# ColdBlock_PID_Main01.net
KiCad netlist of a schematic drawn in Altium Designer
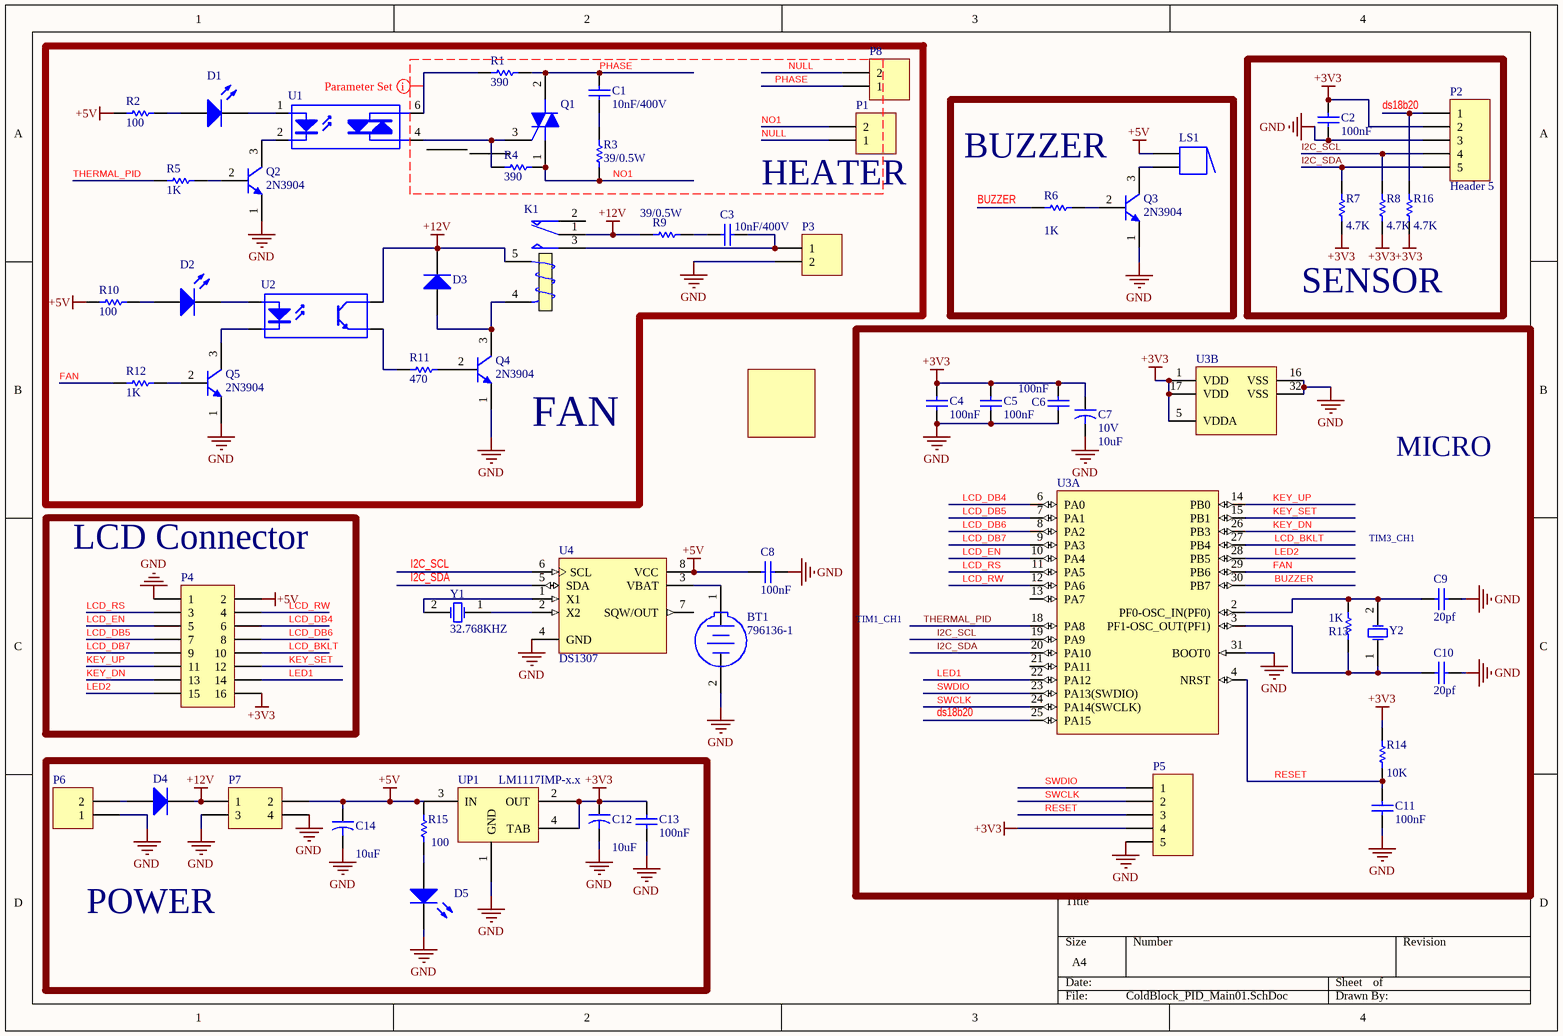
[diagram p0: ColdBlock_PID_Main01.SchDoc]

(export (version "E")
  (design (tool "Eeschema 10.0.6"))
  (components
    (comp (ref "*") (value "Logo") (footprint "LOGO_PARS_TOP") (libsource (lib "Mofidi3D") (part "Logo")))
    (comp (ref "BT1")
      (value "796136-1")
      (footprint "BTH2032_dip")
      (description "Battery Connector, 1 Cell, CR2032, 2-Pin SMD, RoHS, Tape and Reel")
      (libsource (lib "TE PCB Connectors") (part "796136-1"))
    )
    (comp (ref "C1")
      (value "10nF/400V")
      (footprint "Cap_polyester_400V")
      (description "Capacitor")
      (fields (field (name "PUBLISHER") "Altium Limited"))
      (libsource (lib "Miscellaneous Devices") (part "Cap"))
    )
    (comp (ref "C2")
      (value "100nF")
      (footprint "CAP_MLCC_RAD_0.1")
      (description "Capacitor")
      (fields (field (name "Comment") "Cap") (field (name "PUBLISHER") "Altium Limited"))
      (libsource (lib "Miscellaneous Devices") (part "Cap"))
    )
    (comp (ref "C3")
      (value "10nF/400V")
      (footprint "Cap_polyester_400V")
      (description "Capacitor")
      (fields (field (name "PUBLISHER") "Altium Limited"))
      (libsource (lib "Miscellaneous Devices") (part "Cap"))
    )
    (comp (ref "C4")
      (value "100nF")
      (footprint "CAP_MLCC_RAD_0.1")
      (description "Capacitor")
      (fields (field (name "Comment") "Cap") (field (name "PUBLISHER") "Altium Limited"))
      (libsource (lib "Miscellaneous Devices") (part "Cap"))
    )
    (comp (ref "C5")
      (value "100nF")
      (footprint "CAP_MLCC_RAD_0.1")
      (description "Capacitor")
      (fields (field (name "Comment") "Cap") (field (name "PUBLISHER") "Altium Limited"))
      (libsource (lib "Miscellaneous Devices") (part "Cap"))
    )
    (comp (ref "C6")
      (value "100nF")
      (footprint "CAP_MLCC_RAD_0.1")
      (description "Capacitor")
      (fields (field (name "Comment") "Cap") (field (name "PUBLISHER") "Altium Limited"))
      (libsource (lib "Miscellaneous Devices") (part "Cap"))
    )
    (comp (ref "C7")
      (value "10V")
      (footprint "Cap electrolitic radial 5x11-2")
      (description "Capacitor")
      (fields (field (name "ALTIUM_VALUE") "10uF") (field (name "PUBLISHER") "Altium Limited"))
      (libsource (lib "Miscellaneous Devices") (part "Cap2"))
    )
    (comp (ref "C8")
      (value "100nF")
      (footprint "CAP_MLCC_RAD_0.1")
      (description "Capacitor")
      (fields (field (name "Comment") "Cap") (field (name "PUBLISHER") "Altium Limited"))
      (libsource (lib "Miscellaneous Devices") (part "Cap"))
    )
    (comp (ref "C9")
      (value "20pf")
      (footprint "CAP_MLCC_RAD_0.1")
      (description "Capacitor")
      (fields (field (name "Comment") "Cap") (field (name "PUBLISHER") "Altium Limited"))
      (libsource (lib "Miscellaneous Devices") (part "Cap"))
    )
    (comp (ref "C10")
      (value "20pf")
      (footprint "CAP_MLCC_RAD_0.1")
      (description "Capacitor")
      (fields (field (name "Comment") "Cap") (field (name "PUBLISHER") "Altium Limited"))
      (libsource (lib "Miscellaneous Devices") (part "Cap"))
    )
    (comp (ref "C11")
      (value "100nF")
      (footprint "CAP_MLCC_RAD_0.1")
      (description "Capacitor")
      (fields (field (name "Comment") "Cap") (field (name "PUBLISHER") "Altium Limited"))
      (libsource (lib "Miscellaneous Devices") (part "Cap"))
    )
    (comp (ref "C12")
      (value "10uF")
      (footprint "Cap electrolitic radial 5x11-2")
      (description "Capacitor")
      (fields (field (name "Comment") "16V") (field (name "PUBLISHER") "Altium Limited"))
      (libsource (lib "Miscellaneous Devices") (part "Cap2"))
    )
    (comp (ref "C13")
      (value "100nF")
      (footprint "CAP_MLCC_RAD_0.1")
      (description "Capacitor")
      (fields (field (name "Comment") "Cap") (field (name "PUBLISHER") "Altium Limited"))
      (libsource (lib "Miscellaneous Devices") (part "Cap"))
    )
    (comp (ref "C14")
      (value "10uF")
      (footprint "Cap electrolitic radial 5x11-2")
      (description "Capacitor")
      (fields (field (name "Comment") "25 V") (field (name "PUBLISHER") "Altium Limited"))
      (libsource (lib "Miscellaneous Devices") (part "Cap2"))
    )
    (comp (ref "D1")
      (value "LED1")
      (footprint "LED5MM_BLUE")
      (description "Typical RED GaAs LED")
      (fields (field (name "PUBLISHER") "Altium Limited"))
      (libsource (lib "Miscellaneous Devices") (part "LED1"))
    )
    (comp (ref "D2")
      (value "LED1")
      (footprint "LED5MM_RED")
      (description "Typical RED GaAs LED")
      (fields (field (name "PUBLISHER") "Altium Limited"))
      (libsource (lib "Miscellaneous Devices") (part "LED1"))
    )
    (comp (ref "D3")
      (value "Diode 1N4007")
      (footprint "do-204al")
      (description "1 Amp General Purpose Rectifier")
      (fields (field (name "PUBLISHER") "Altium Limited"))
      (libsource (lib "Miscellaneous Devices") (part "Diode 1N4007"))
    )
    (comp (ref "D4")
      (value "1N4007")
      (footprint "DO-204AL")
      (description "Default Diode")
      (fields (field (name "PUBLISHER") "Altium Limited"))
      (libsource (lib "Miscellaneous Devices") (part "Diode"))
    )
    (comp (ref "D5")
      (value "LED0")
      (footprint "LED5MM_BLUE")
      (description "Typical INFRARED GaAs LED")
      (fields (field (name "PUBLISHER") "Altium Limited"))
      (libsource (lib "Miscellaneous Devices") (part "LED0"))
    )
    (comp (ref "K1")
      (value "Relay/12V")
      (footprint "Mofidi3D:Relay 18.85x15.35x15.70")
      (description "SPDT Relay")
      (fields (field (name "PUBLISHER") "Altium Limited"))
      (libsource (lib "Miscellaneous Devices") (part "Relay"))
    )
    (comp (ref "LS1")
      (value "Buzzer")
      (footprint "BUZZER_12A05")
      (description "Magnetic Transducer Buzzer")
      (fields (field (name "PUBLISHER") "Altium Limited"))
      (libsource (lib "Miscellaneous Devices") (part "Buzzer"))
    )
    (comp (ref "P1")
      (value "Header 2")
      (footprint "KF301 2PIN")
      (description "Header, 2-Pin")
      (fields (field (name "PUBLISHER") "Altium Limited"))
      (libsource (lib "") (part "Header 2_1"))
    )
    (comp (ref "P2")
      (value "Header 5")
      (footprint "HDR1X5")
      (description "Header, 5-Pin")
      (fields (field (name "PUBLISHER") "Altium Limited"))
      (libsource (lib "Miscellaneous Connectors") (part "Header 5"))
    )
    (comp (ref "P3")
      (value "Header 2")
      (footprint "KF301 2PIN")
      (description "Header, 2-Pin")
      (fields (field (name "PUBLISHER") "Altium Limited"))
      (libsource (lib "") (part "Header 2_2"))
    )
    (comp (ref "P4")
      (value "Header 8X2")
      (footprint "IDC2.54_16PIN")
      (description "Header, 8-Pin, Dual row")
      (fields (field (name "PUBLISHER") "Altium Limited"))
      (libsource (lib "Miscellaneous Connectors") (part "Header 8X2"))
    )
    (comp (ref "P5")
      (value "Header 5")
      (footprint "HDR_1x6")
      (description "Header, 5-Pin")
      (fields (field (name "PUBLISHER") "Altium Limited"))
      (libsource (lib "Miscellaneous Connectors") (part "Header 5"))
    )
    (comp (ref "P6")
      (value "Header 2")
      (footprint "KF301 2PIN")
      (description "Header, 2-Pin")
      (fields (field (name "PUBLISHER") "Altium Limited"))
      (libsource (lib "Miscellaneous Connectors") (part "Header 2"))
    )
    (comp (ref "P7")
      (value "MINI-360")
      (footprint "MINI360-DCDC")
      (description "Header, 2-Pin, Dual row")
      (fields (field (name "PUBLISHER") "Altium Limited"))
      (libsource (lib "Miscellaneous Connectors") (part "Header 2X2"))
    )
    (comp (ref "P8")
      (value "Header 2")
      (footprint "KF301 2PIN")
      (description "Header, 2-Pin")
      (fields (field (name "PUBLISHER") "Altium Limited"))
      (libsource (lib "") (part "Header 2_1"))
    )
    (comp (ref "Q1")
      (value "BT139")
      (footprint "TO-220 AB")
      (description "Silicon Bidirectional Triode Thyristor")
      (fields (field (name "PUBLISHER") "Altium Limited"))
      (libsource (lib "Miscellaneous Devices") (part "Triac"))
    )
    (comp (ref "Q2")
      (value "2N3904")
      (footprint "TO-92 STR")
      (description "NPN General Purpose Amplifier")
      (fields (field (name "PUBLISHER") "Altium Limited"))
      (libsource (lib "Miscellaneous Devices") (part "2N3904"))
    )
    (comp (ref "Q3")
      (value "2N3904")
      (footprint "TO-92 STR")
      (description "NPN General Purpose Amplifier")
      (fields (field (name "PUBLISHER") "Altium Limited"))
      (libsource (lib "Miscellaneous Devices") (part "2N3904"))
    )
    (comp (ref "Q4")
      (value "2N3904")
      (footprint "TO-92 STR")
      (description "NPN General Purpose Amplifier")
      (fields (field (name "PUBLISHER") "Altium Limited"))
      (libsource (lib "Miscellaneous Devices") (part "2N3904"))
    )
    (comp (ref "Q5")
      (value "2N3904")
      (footprint "TO-92 STR")
      (description "NPN General Purpose Amplifier")
      (fields (field (name "PUBLISHER") "Altium Limited"))
      (libsource (lib "Miscellaneous Devices") (part "2N3904"))
    )
    (comp (ref "R1")
      (value "390")
      (footprint "Axial 0_5W 5_0mm")
      (description "Resistor")
      (fields (field (name "Comment") "Res1") (field (name "PUBLISHER") "Altium Limited"))
      (libsource (lib "Miscellaneous Devices") (part "Res1"))
    )
    (comp (ref "R2")
      (value "100")
      (footprint "Axial 0_25 W, 0_4 IN LEAD PITCH")
      (description "Resistor")
      (fields (field (name "Comment") "Res1") (field (name "PUBLISHER") "Altium Limited"))
      (libsource (lib "Miscellaneous Devices") (part "Res1"))
    )
    (comp (ref "R3")
      (value "39/0.5W")
      (footprint "Axial 0_5W 5_0mm")
      (description "Resistor")
      (fields (field (name "Comment") "Res1") (field (name "PUBLISHER") "Altium Limited"))
      (libsource (lib "Miscellaneous Devices") (part "Res1"))
    )
    (comp (ref "R4")
      (value "390")
      (footprint "Axial 0_5W 5_0mm")
      (description "Resistor")
      (fields (field (name "Comment") "Res1") (field (name "PUBLISHER") "Altium Limited"))
      (libsource (lib "Miscellaneous Devices") (part "Res1"))
    )
    (comp (ref "R5")
      (value "1K")
      (footprint "Axial 0_25 W, 0_4 IN LEAD PITCH")
      (description "Resistor")
      (fields (field (name "Comment") "Res1") (field (name "PUBLISHER") "Altium Limited"))
      (libsource (lib "Miscellaneous Devices") (part "Res1"))
    )
    (comp (ref "R6")
      (value "1K")
      (footprint "Axial 0_25 W, 0_4 IN LEAD PITCH")
      (description "Resistor")
      (fields (field (name "Comment") "Res1") (field (name "PUBLISHER") "Altium Limited"))
      (libsource (lib "Miscellaneous Devices") (part "Res1"))
    )
    (comp (ref "R7")
      (value "4.7K")
      (footprint "Axial 0_25 W, 0_4 IN LEAD PITCH")
      (description "Resistor")
      (fields (field (name "Comment") "Res1") (field (name "PUBLISHER") "Altium Limited"))
      (libsource (lib "Miscellaneous Devices") (part "Res1"))
    )
    (comp (ref "R8")
      (value "4.7K")
      (footprint "Axial 0_25 W, 0_4 IN LEAD PITCH")
      (description "Resistor")
      (fields (field (name "Comment") "Res1") (field (name "PUBLISHER") "Altium Limited"))
      (libsource (lib "Miscellaneous Devices") (part "Res1"))
    )
    (comp (ref "R9")
      (value "39/0.5W")
      (footprint "Axial 0_5W 5_0mm")
      (description "Resistor")
      (fields (field (name "Comment") "Res1") (field (name "PUBLISHER") "Altium Limited"))
      (libsource (lib "Miscellaneous Devices") (part "Res1"))
    )
    (comp (ref "R10")
      (value "100")
      (footprint "Axial 0_25 W, 0_4 IN LEAD PITCH")
      (description "Resistor")
      (fields (field (name "Comment") "Res1") (field (name "PUBLISHER") "Altium Limited"))
      (libsource (lib "Miscellaneous Devices") (part "Res1"))
    )
    (comp (ref "R11")
      (value "470")
      (footprint "Axial 0_25 W, 0_4 IN LEAD PITCH")
      (description "Resistor")
      (fields (field (name "Comment") "Res1") (field (name "PUBLISHER") "Altium Limited"))
      (libsource (lib "Miscellaneous Devices") (part "Res1"))
    )
    (comp (ref "R12")
      (value "1K")
      (footprint "Axial 0_25 W, 0_4 IN LEAD PITCH")
      (description "Resistor")
      (fields (field (name "Comment") "Res1") (field (name "PUBLISHER") "Altium Limited"))
      (libsource (lib "Miscellaneous Devices") (part "Res1"))
    )
    (comp (ref "R13")
      (value "1K")
      (footprint "Axial 0_25 W, 0_4 IN LEAD PITCH")
      (description "Resistor")
      (fields (field (name "Comment") "Res1") (field (name "PUBLISHER") "Altium Limited"))
      (libsource (lib "Miscellaneous Devices") (part "Res1"))
    )
    (comp (ref "R14")
      (value "10K")
      (footprint "Axial 0_25 W, 0_4 IN LEAD PITCH")
      (description "Resistor")
      (fields (field (name "Comment") "Res1") (field (name "PUBLISHER") "Altium Limited"))
      (libsource (lib "Miscellaneous Devices") (part "Res1"))
    )
    (comp (ref "R15")
      (value "100")
      (footprint "Axial 0_25 W, 0_4 IN LEAD PITCH")
      (description "Resistor")
      (fields (field (name "Comment") "Res1") (field (name "PUBLISHER") "Altium Limited"))
      (libsource (lib "Miscellaneous Devices") (part "Res1"))
    )
    (comp (ref "R16")
      (value "4.7K")
      (footprint "Axial 0_25 W, 0_4 IN LEAD PITCH")
      (description "Resistor")
      (fields (field (name "Comment") "Res1") (field (name "PUBLISHER") "Altium Limited"))
      (libsource (lib "Miscellaneous Devices") (part "Res1"))
    )
    (comp (ref "U1")
      (value "MOC3063")
      (footprint "MOC3063")
      (description "Opto-Triac")
      (fields (field (name "PUBLISHER") "Altium Limited"))
      (libsource (lib "Miscellaneous Devices") (part "Opto TRIAC"))
    )
    (comp (ref "U2")
      (value "PC817")
      (footprint "DIP_4")
      (description "4-Pin Phototransistor Optocoupler")
      (fields (field (name "PUBLISHER") "Altium Limited"))
      (libsource (lib "Miscellaneous Devices") (part "Optoisolator1"))
    )
    (comp (ref "U3")
      (value "STM32F030K6T6")
      (footprint "STM-LQFP32_N")
      (libsource (lib "STMicroelectronics STM32 F0") (part "STM32F030K6T6"))
    )
    (comp (ref "U4")
      (value "DS1307")
      (footprint "DIP8")
      (description "64 X 8 Serial Real-Time Clock")
      (fields (field (name "PUBLISHER") "Altium Limited"))
      (libsource (lib "Dallas Peripheral Real Time Clock") (part "DS1307"))
    )
    (comp (ref "UP1")
      (value "LM1117IMP-x.x")
      (footprint "SOT223_4")
      (description "x.x Volt, 800mA Low-Dropout Linear Regulator, 4-pin SOT-223")
      (fields (field (name "DESIGNER") "Abbas Basereh"))
      (libsource (lib "Mofidi3D") (part "LM1117IMP-x.x"))
    )
    (comp (ref "Y1")
      (value "32.768KHZ")
      (footprint "Crystal_NC308")
      (description "Crystal Oscillator")
      (fields (field (name "PUBLISHER") "Altium Limited"))
      (libsource (lib "ECS Crystal Oscillator") (part "ECS-110-S-5P"))
    )
    (comp (ref "Y2")
      (value "8MHz")
      (footprint "CRYSTAL Small")
      (description "Crystal Oscillator")
      (fields (field (name "PUBLISHER") "Altium Limited"))
      (libsource (lib "ECS Crystal Oscillator") (part "ECS-110-S-5P"))
    )
  )
  (nets
    (net (code "1") (name "+3V3") (class "Default")
      (node (ref "C12") (pin "1") (pinfunction "1_1") (pintype "passive"))
      (node (ref "C13") (pin "2") (pinfunction "2_2") (pintype "passive"))
      (node (ref "C2") (pin "2") (pinfunction "2_2") (pintype "passive"))
      (node (ref "C4") (pin "2") (pinfunction "2_2") (pintype "passive"))
      (node (ref "C5") (pin "2") (pinfunction "2_2") (pintype "passive"))
      (node (ref "C6") (pin "2") (pinfunction "2_2") (pintype "passive"))
      (node (ref "C7") (pin "1") (pinfunction "1_1") (pintype "passive"))
      (node (ref "P2") (pin "2") (pinfunction "2_2") (pintype "passive"))
      (node (ref "P4") (pin "16") (pinfunction "16_16") (pintype "passive"))
      (node (ref "P5") (pin "4") (pinfunction "4_4") (pintype "passive"))
      (node (ref "R14") (pin "1") (pinfunction "1_1") (pintype "passive"))
      (node (ref "R16") (pin "2") (pinfunction "2_2") (pintype "passive"))
      (node (ref "R7") (pin "2") (pinfunction "2_2") (pintype "passive"))
      (node (ref "R8") (pin "2") (pinfunction "2_2") (pintype "passive"))
      (node (ref "U3") (pin "1") (pinfunction "VDD_1") (pintype "power_in"))
      (node (ref "U3") (pin "17") (pinfunction "VDD_17") (pintype "power_in"))
      (node (ref "U3") (pin "5") (pinfunction "VDDA_5") (pintype "power_in"))
      (node (ref "UP1") (pin "2") (pinfunction "OUT_2") (pintype "power_in"))
      (node (ref "UP1") (pin "4") (pinfunction "TAB_4") (pintype "power_in"))
    )
    (net (code "2") (name "+5V") (class "Default")
      (node (ref "C14") (pin "1") (pinfunction "1_1") (pintype "passive"))
      (node (ref "C8") (pin "1") (pinfunction "1_1") (pintype "passive"))
      (node (ref "LS1") (pin "1") (pinfunction "1_1") (pintype "passive"))
      (node (ref "P4") (pin "2") (pinfunction "2_2") (pintype "passive"))
      (node (ref "P7") (pin "2") (pinfunction "2_2") (pintype "passive"))
      (node (ref "R10") (pin "1") (pinfunction "1_1") (pintype "passive"))
      (node (ref "R15") (pin "2") (pinfunction "2_2") (pintype "passive"))
      (node (ref "R2") (pin "1") (pinfunction "1_1") (pintype "passive"))
      (node (ref "U4") (pin "8") (pinfunction "VCC_8") (pintype "power_in"))
      (node (ref "UP1") (pin "3") (pinfunction "IN_3") (pintype "power_in"))
    )
    (net (code "3") (name "+12V") (class "Default")
      (node (ref "D3") (pin "2") (pinfunction "K_2") (pintype "passive"))
      (node (ref "D4") (pin "2") (pinfunction "K_2") (pintype "passive"))
      (node (ref "K1") (pin "1") (pinfunction "COM_1") (pintype "passive"))
      (node (ref "K1") (pin "5") (pinfunction "T1_5") (pintype "passive"))
      (node (ref "P7") (pin "1") (pinfunction "1_1") (pintype "passive"))
      (node (ref "R9") (pin "1") (pinfunction "1_1") (pintype "passive"))
      (node (ref "U2") (pin "4") (pinfunction "C_4") (pintype "passive"))
    )
    (net (code "4") (name "/BUZZER") (class "Default")
      (node (ref "R6") (pin "1") (pinfunction "1_1") (pintype "passive"))
      (node (ref "U3") (pin "30") (pinfunction "PB7_30") (pintype "bidirectional"))
    )
    (net (code "5") (name "/FAN") (class "Default")
      (node (ref "R12") (pin "2") (pinfunction "2_2") (pintype "passive"))
      (node (ref "U3") (pin "29") (pinfunction "PB6_29") (pintype "bidirectional"))
    )
    (net (code "6") (name "/I2C_SCL") (class "Default")
      (node (ref "P2") (pin "4") (pinfunction "4_4") (pintype "passive"))
      (node (ref "R8") (pin "1") (pinfunction "1_1") (pintype "passive"))
      (node (ref "U3") (pin "19") (pinfunction "PA9_19") (pintype "bidirectional"))
      (node (ref "U4") (pin "6") (pinfunction "SCL_6") (pintype "input"))
    )
    (net (code "7") (name "/I2C_SDA") (class "Default")
      (node (ref "P2") (pin "5") (pinfunction "5_5") (pintype "passive"))
      (node (ref "R7") (pin "1") (pinfunction "1_1") (pintype "passive"))
      (node (ref "U3") (pin "20") (pinfunction "PA10_20") (pintype "bidirectional"))
      (node (ref "U4") (pin "5") (pinfunction "SDA_5") (pintype "bidirectional"))
    )
    (net (code "8") (name "/KEY_DN") (class "Default")
      (node (ref "P4") (pin "13") (pinfunction "13_13") (pintype "passive"))
      (node (ref "U3") (pin "26") (pinfunction "PB3_26") (pintype "bidirectional"))
    )
    (net (code "9") (name "/KEY_SET") (class "Default")
      (node (ref "P4") (pin "12") (pinfunction "12_12") (pintype "passive"))
      (node (ref "U3") (pin "15") (pinfunction "PB1_15") (pintype "bidirectional"))
    )
    (net (code "10") (name "/KEY_UP") (class "Default")
      (node (ref "P4") (pin "11") (pinfunction "11_11") (pintype "passive"))
      (node (ref "U3") (pin "14") (pinfunction "PB0_14") (pintype "bidirectional"))
    )
    (net (code "11") (name "/LCD_BKLT") (class "Default")
      (node (ref "P4") (pin "10") (pinfunction "10_10") (pintype "passive"))
      (node (ref "U3") (pin "27") (pinfunction "PB4_27") (pintype "bidirectional"))
    )
    (net (code "12") (name "/LCD_DB4") (class "Default")
      (node (ref "P4") (pin "6") (pinfunction "6_6") (pintype "passive"))
      (node (ref "U3") (pin "6") (pinfunction "PA0_6") (pintype "bidirectional"))
    )
    (net (code "13") (name "/LCD_DB5") (class "Default")
      (node (ref "P4") (pin "7") (pinfunction "7_7") (pintype "passive"))
      (node (ref "U3") (pin "7") (pinfunction "PA1_7") (pintype "bidirectional"))
    )
    (net (code "14") (name "/LCD_DB6") (class "Default")
      (node (ref "P4") (pin "8") (pinfunction "8_8") (pintype "passive"))
      (node (ref "U3") (pin "8") (pinfunction "PA2_8") (pintype "bidirectional"))
    )
    (net (code "15") (name "/LCD_DB7") (class "Default")
      (node (ref "P4") (pin "9") (pinfunction "9_9") (pintype "passive"))
      (node (ref "U3") (pin "9") (pinfunction "PA3_9") (pintype "bidirectional"))
    )
    (net (code "16") (name "/LCD_EN") (class "Default")
      (node (ref "P4") (pin "5") (pinfunction "5_5") (pintype "passive"))
      (node (ref "U3") (pin "10") (pinfunction "PA4_10") (pintype "bidirectional"))
    )
    (net (code "17") (name "/LCD_RS") (class "Default")
      (node (ref "P4") (pin "3") (pinfunction "3_3") (pintype "passive"))
      (node (ref "U3") (pin "11") (pinfunction "PA5_11") (pintype "bidirectional"))
    )
    (net (code "18") (name "/LCD_RW") (class "Default")
      (node (ref "P4") (pin "4") (pinfunction "4_4") (pintype "passive"))
      (node (ref "U3") (pin "12") (pinfunction "PA6_12") (pintype "bidirectional"))
    )
    (net (code "19") (name "/LED1") (class "Default")
      (node (ref "P4") (pin "14") (pinfunction "14_14") (pintype "passive"))
      (node (ref "U3") (pin "22") (pinfunction "PA12_22") (pintype "bidirectional"))
    )
    (net (code "20") (name "/LED2") (class "Default")
      (node (ref "P4") (pin "15") (pinfunction "15_15") (pintype "passive"))
      (node (ref "U3") (pin "28") (pinfunction "PB5_28") (pintype "bidirectional"))
    )
    (net (code "21") (name "/NO1") (class "Default")
      (node (ref "P1") (pin "2") (pinfunction "2_2") (pintype "passive"))
      (node (ref "Q1") (pin "1") (pinfunction "M1_1") (pintype "passive"))
      (node (ref "R3") (pin "1") (pinfunction "1_1") (pintype "passive"))
      (node (ref "R4") (pin "1") (pinfunction "1_1") (pintype "passive"))
    )
    (net (code "22") (name "/NULL") (class "Default")
      (node (ref "P1") (pin "1") (pinfunction "1_1") (pintype "passive"))
      (node (ref "P8") (pin "2") (pinfunction "2_2") (pintype "passive"))
    )
    (net (code "23") (name "/PHASE") (class "Default")
      (node (ref "C1") (pin "1") (pinfunction "1_1") (pintype "passive"))
      (node (ref "P8") (pin "1") (pinfunction "1_1") (pintype "passive"))
      (node (ref "Q1") (pin "2") (pinfunction "M2_2") (pintype "passive"))
      (node (ref "R1") (pin "1") (pinfunction "1_1") (pintype "passive"))
    )
    (net (code "24") (name "/RESET") (class "Default")
      (node (ref "C11") (pin "1") (pinfunction "1_1") (pintype "passive"))
      (node (ref "P5") (pin "3") (pinfunction "3_3") (pintype "passive"))
      (node (ref "R14") (pin "2") (pinfunction "2_2") (pintype "passive"))
      (node (ref "U3") (pin "4") (pinfunction "NRST_4") (pintype "bidirectional"))
    )
    (net (code "25") (name "/SWCLK") (class "Default")
      (node (ref "P5") (pin "2") (pinfunction "2_2") (pintype "passive"))
      (node (ref "U3") (pin "24") (pinfunction "PA14(SWCLK)_24") (pintype "bidirectional"))
    )
    (net (code "26") (name "/SWDIO") (class "Default")
      (node (ref "P5") (pin "1") (pinfunction "1_1") (pintype "passive"))
      (node (ref "U3") (pin "23") (pinfunction "PA13(SWDIO)_23") (pintype "bidirectional"))
    )
    (net (code "27") (name "/THERMAL_PID") (class "Default")
      (node (ref "R5") (pin "1") (pinfunction "1_1") (pintype "passive"))
      (node (ref "U3") (pin "18") (pinfunction "PA8_18") (pintype "bidirectional"))
    )
    (net (code "28") (name "/ds18b20") (class "Default")
      (node (ref "P2") (pin "1") (pinfunction "1_1") (pintype "passive"))
      (node (ref "R16") (pin "1") (pinfunction "1_1") (pintype "passive"))
      (node (ref "U3") (pin "25") (pinfunction "PA15_25") (pintype "bidirectional"))
    )
    (net (code "29") (name "GND") (class "Default")
      (node (ref "BT1") (pin "2") (pinfunction "-_2") (pintype "passive"))
      (node (ref "C10") (pin "1") (pinfunction "1_1") (pintype "passive"))
      (node (ref "C11") (pin "2") (pinfunction "2_2") (pintype "passive"))
      (node (ref "C12") (pin "2") (pinfunction "2_2") (pintype "passive"))
      (node (ref "C13") (pin "1") (pinfunction "1_1") (pintype "passive"))
      (node (ref "C14") (pin "2") (pinfunction "2_2") (pintype "passive"))
      (node (ref "C2") (pin "1") (pinfunction "1_1") (pintype "passive"))
      (node (ref "C4") (pin "1") (pinfunction "1_1") (pintype "passive"))
      (node (ref "C5") (pin "1") (pinfunction "1_1") (pintype "passive"))
      (node (ref "C6") (pin "1") (pinfunction "1_1") (pintype "passive"))
      (node (ref "C7") (pin "2") (pinfunction "2_2") (pintype "passive"))
      (node (ref "C8") (pin "2") (pinfunction "2_2") (pintype "passive"))
      (node (ref "C9") (pin "1") (pinfunction "1_1") (pintype "passive"))
      (node (ref "D5") (pin "2") (pinfunction "K_2") (pintype "passive"))
      (node (ref "P2") (pin "3") (pinfunction "3_3") (pintype "passive"))
      (node (ref "P3") (pin "2") (pinfunction "2_2") (pintype "passive"))
      (node (ref "P4") (pin "1") (pinfunction "1_1") (pintype "passive"))
      (node (ref "P5") (pin "5") (pinfunction "5_5") (pintype "passive"))
      (node (ref "P6") (pin "1") (pinfunction "1_1") (pintype "passive"))
      (node (ref "P7") (pin "3") (pinfunction "3_3") (pintype "passive"))
      (node (ref "P7") (pin "4") (pinfunction "4_4") (pintype "passive"))
      (node (ref "Q2") (pin "1") (pinfunction "E_1") (pintype "passive"))
      (node (ref "Q3") (pin "1") (pinfunction "E_1") (pintype "passive"))
      (node (ref "Q4") (pin "1") (pinfunction "E_1") (pintype "passive"))
      (node (ref "Q5") (pin "1") (pinfunction "E_1") (pintype "passive"))
      (node (ref "U3") (pin "16") (pinfunction "VSS_16") (pintype "power_in"))
      (node (ref "U3") (pin "31") (pinfunction "BOOT0_31") (pintype "input"))
      (node (ref "U3") (pin "32") (pinfunction "VSS_32") (pintype "power_in"))
      (node (ref "U4") (pin "4") (pinfunction "GND_4") (pintype "power_in"))
      (node (ref "UP1") (pin "1") (pinfunction "GND_1") (pintype "power_in"))
    )
    (net (code "30") (name "Net-(BT1-+)") (class "Default")
      (node (ref "BT1") (pin "1") (pinfunction "+_1") (pintype "passive"))
      (node (ref "U4") (pin "3") (pinfunction "VBAT_3") (pintype "power_in"))
    )
    (net (code "31") (name "Net-(C1-Pad2)") (class "Default")
      (node (ref "C1") (pin "2") (pinfunction "2_2") (pintype "passive"))
      (node (ref "R3") (pin "2") (pinfunction "2_2") (pintype "passive"))
    )
    (net (code "32") (name "Net-(C3-Pad2)") (class "Default")
      (node (ref "C3") (pin "2") (pinfunction "2_2") (pintype "passive"))
      (node (ref "R9") (pin "2") (pinfunction "2_2") (pintype "passive"))
    )
    (net (code "33") (name "Net-(D1-A)") (class "Default")
      (node (ref "D1") (pin "1") (pinfunction "A_1") (pintype "passive"))
      (node (ref "R2") (pin "2") (pinfunction "2_2") (pintype "passive"))
    )
    (net (code "34") (name "Net-(D1-K)") (class "Default")
      (node (ref "D1") (pin "2") (pinfunction "K_2") (pintype "passive"))
      (node (ref "U1") (pin "1") (pinfunction "A_1") (pintype "passive"))
    )
    (net (code "35") (name "Net-(D2-A)") (class "Default")
      (node (ref "D2") (pin "1") (pinfunction "A_1") (pintype "passive"))
      (node (ref "R10") (pin "2") (pinfunction "2_2") (pintype "passive"))
    )
    (net (code "36") (name "Net-(D2-K)") (class "Default")
      (node (ref "D2") (pin "2") (pinfunction "K_2") (pintype "passive"))
      (node (ref "U2") (pin "1") (pinfunction "A_1") (pintype "passive"))
    )
    (net (code "37") (name "Net-(D3-A)") (class "Default")
      (node (ref "D3") (pin "1") (pinfunction "A_1") (pintype "passive"))
      (node (ref "K1") (pin "4") (pinfunction "T2_4") (pintype "passive"))
      (node (ref "Q4") (pin "3") (pinfunction "C_3") (pintype "passive"))
    )
    (net (code "38") (name "Net-(D4-A)") (class "Default")
      (node (ref "D4") (pin "1") (pinfunction "A_1") (pintype "passive"))
      (node (ref "P6") (pin "2") (pinfunction "2_2") (pintype "passive"))
    )
    (net (code "39") (name "Net-(D5-A)") (class "Default")
      (node (ref "D5") (pin "1") (pinfunction "A_1") (pintype "passive"))
      (node (ref "R15") (pin "1") (pinfunction "1_1") (pintype "passive"))
    )
    (net (code "40") (name "Net-(K1-NO)") (class "Default")
      (node (ref "C3") (pin "1") (pinfunction "1_1") (pintype "passive"))
      (node (ref "K1") (pin "3") (pinfunction "NO_3") (pintype "passive"))
      (node (ref "P3") (pin "1") (pinfunction "1_1") (pintype "passive"))
    )
    (net (code "41") (name "Net-(Q1-G)") (class "Default")
      (node (ref "Q1") (pin "3") (pinfunction "G_3") (pintype "passive"))
      (node (ref "R4") (pin "2") (pinfunction "2_2") (pintype "passive"))
      (node (ref "U1") (pin "4") (pinfunction "A/K_4") (pintype "passive"))
    )
    (net (code "42") (name "Net-(Q2-B)") (class "Default")
      (node (ref "Q2") (pin "2") (pinfunction "B_2") (pintype "passive"))
      (node (ref "R5") (pin "2") (pinfunction "2_2") (pintype "passive"))
    )
    (net (code "43") (name "Net-(Q2-C)") (class "Default")
      (node (ref "Q2") (pin "3") (pinfunction "C_3") (pintype "passive"))
      (node (ref "U1") (pin "2") (pinfunction "K_2") (pintype "passive"))
    )
    (net (code "44") (name "Net-(Q3-B)") (class "Default")
      (node (ref "Q3") (pin "2") (pinfunction "B_2") (pintype "passive"))
      (node (ref "R6") (pin "2") (pinfunction "2_2") (pintype "passive"))
    )
    (net (code "45") (name "Net-(Q3-C)") (class "Default")
      (node (ref "LS1") (pin "2") (pinfunction "2_2") (pintype "passive"))
      (node (ref "Q3") (pin "3") (pinfunction "C_3") (pintype "passive"))
    )
    (net (code "46") (name "Net-(Q4-B)") (class "Default")
      (node (ref "Q4") (pin "2") (pinfunction "B_2") (pintype "passive"))
      (node (ref "R11") (pin "1") (pinfunction "1_1") (pintype "passive"))
    )
    (net (code "47") (name "Net-(Q5-B)") (class "Default")
      (node (ref "Q5") (pin "2") (pinfunction "B_2") (pintype "passive"))
      (node (ref "R12") (pin "1") (pinfunction "1_1") (pintype "passive"))
    )
    (net (code "48") (name "Net-(Q5-C)") (class "Default")
      (node (ref "Q5") (pin "3") (pinfunction "C_3") (pintype "passive"))
      (node (ref "U2") (pin "2") (pinfunction "K_2") (pintype "passive"))
    )
    (net (code "49") (name "Net-(R1-Pad2)") (class "Default")
      (node (ref "R1") (pin "2") (pinfunction "2_2") (pintype "passive"))
      (node (ref "U1") (pin "6") (pinfunction "A/K_6") (pintype "passive"))
    )
    (net (code "50") (name "Net-(U2-E)") (class "Default")
      (node (ref "R11") (pin "2") (pinfunction "2_2") (pintype "passive"))
      (node (ref "U2") (pin "3") (pinfunction "E_3") (pintype "passive"))
    )
    (net (code "51") (name "Net-(U3A-PF0-OSC_IN(PF0))") (class "Default")
      (node (ref "C9") (pin "2") (pinfunction "2_2") (pintype "passive"))
      (node (ref "R13") (pin "2") (pinfunction "2_2") (pintype "passive"))
      (node (ref "U3") (pin "2") (pinfunction "PF0-OSC_IN(PF0)_2") (pintype "bidirectional"))
      (node (ref "Y2") (pin "2") (pinfunction "OSC2_2") (pintype "passive"))
    )
    (net (code "52") (name "Net-(U3A-PF1-OSC_OUT(PF1))") (class "Default")
      (node (ref "C10") (pin "2") (pinfunction "2_2") (pintype "passive"))
      (node (ref "R13") (pin "1") (pinfunction "1_1") (pintype "passive"))
      (node (ref "U3") (pin "3") (pinfunction "PF1-OSC_OUT(PF1)_3") (pintype "bidirectional"))
      (node (ref "Y2") (pin "1") (pinfunction "OSC1_1") (pintype "passive"))
    )
    (net (code "53") (name "Net-(U4-X1)") (class "Default")
      (node (ref "U4") (pin "1") (pinfunction "X1_1") (pintype "input"))
      (node (ref "Y1") (pin "2") (pinfunction "OSC2_2") (pintype "passive"))
    )
    (net (code "54") (name "Net-(U4-X2)") (class "Default")
      (node (ref "U4") (pin "2") (pinfunction "X2_2") (pintype "input"))
      (node (ref "Y1") (pin "1") (pinfunction "OSC1_1") (pintype "passive"))
    )
    (net (code "55") (name "unconnected-(K1-NC-Pad2)") (class "Default")
      (node (ref "K1") (pin "2") (pinfunction "NC_2") (pintype "passive"))
    )
    (net (code "56") (name "unconnected-(U1-NC-Pad3)") (class "Default")
      (node (ref "U1") (pin "3") (pinfunction "NC_3") (pintype "passive"))
    )
    (net (code "57") (name "unconnected-(U1-NC-Pad5)") (class "Default")
      (node (ref "U1") (pin "5") (pinfunction "NC_5") (pintype "passive"))
    )
    (net (code "58") (name "unconnected-(U3A-PA7-Pad13)") (class "Default")
      (node (ref "U3") (pin "13") (pinfunction "PA7_13") (pintype "bidirectional"))
    )
    (net (code "59") (name "unconnected-(U3A-PA11-Pad21)") (class "Default")
      (node (ref "U3") (pin "21") (pinfunction "PA11_21") (pintype "bidirectional"))
    )
    (net (code "60") (name "unconnected-(U4-SQW{slash}OUT-Pad7)") (class "Default")
      (node (ref "U4") (pin "7") (pinfunction "SQW/OUT_7") (pintype "output"))
    )
  )
)
